# n64rgbv1.net
KiCad netlist of a schematic drawn in EAGLE
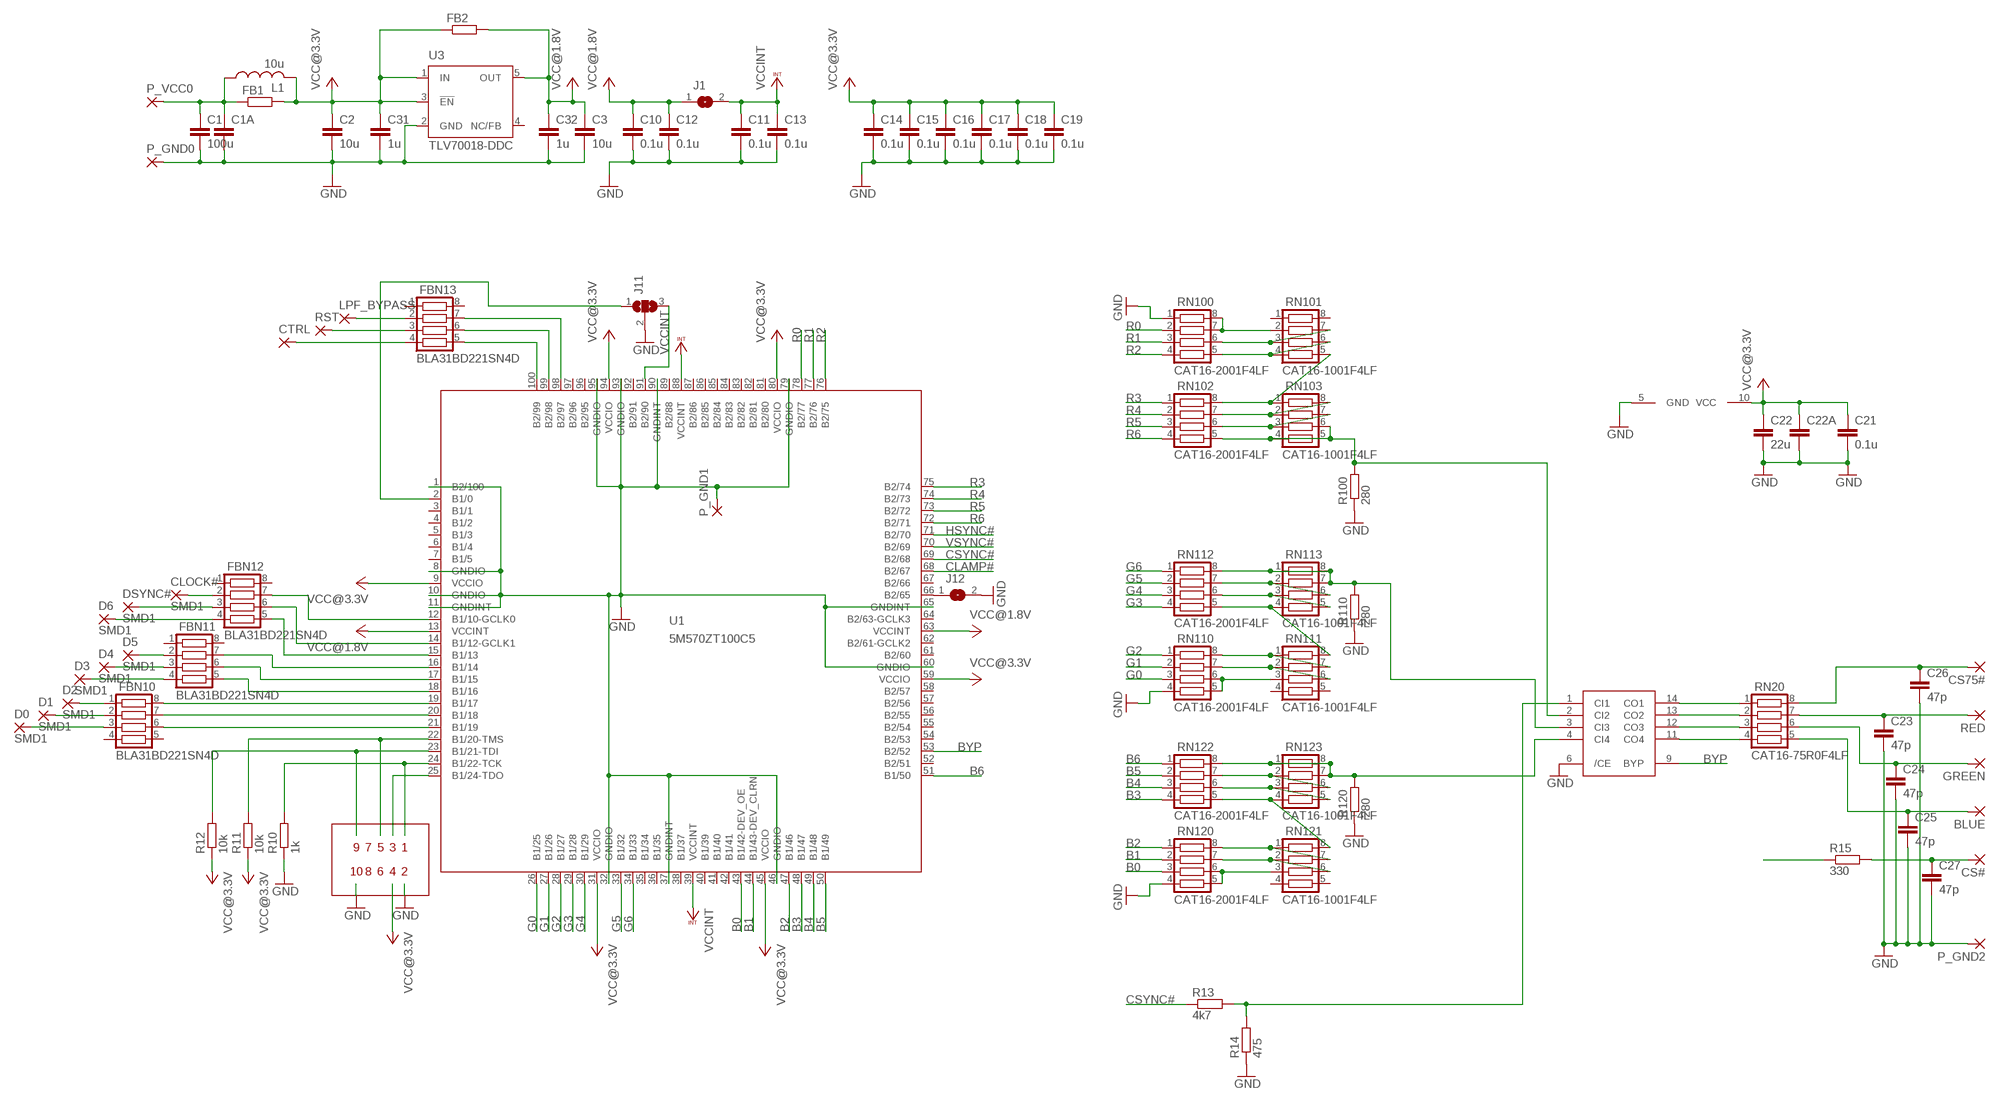
[diagram p0: schematic, sheet 1]

(export (version "E")
  (design (tool "Eeschema 10.0.6"))
  (components
    (comp (ref "BLUE")
      (value "SMD2")
      (footprint "eagle-import:SMD1,27-2,54")
      (libsource (lib "eagle-import") (part "SMD2"))
    )
    (comp (ref "C1")
      (value "100u")
      (footprint "eagle-import:C1206K")
      (libsource (lib "eagle-import") (part "C-EUC1206K"))
    )
    (comp (ref "C1A")
      (value "C-EUC0805")
      (footprint "eagle-import:C0805")
      (libsource (lib "eagle-import") (part "C-EUC0805"))
    )
    (comp (ref "C2")
      (value "10u")
      (footprint "eagle-import:C0805")
      (libsource (lib "eagle-import") (part "C-EUC0805"))
    )
    (comp (ref "C3")
      (value "10u")
      (footprint "eagle-import:C0805")
      (libsource (lib "eagle-import") (part "C-EUC0805"))
    )
    (comp (ref "C10")
      (value "0.1u")
      (footprint "eagle-import:C0603")
      (libsource (lib "eagle-import") (part "C-EUC0603"))
    )
    (comp (ref "C11")
      (value "0.1u")
      (footprint "eagle-import:C0603")
      (libsource (lib "eagle-import") (part "C-EUC0603"))
    )
    (comp (ref "C12")
      (value "0.1u")
      (footprint "eagle-import:C0603")
      (libsource (lib "eagle-import") (part "C-EUC0603"))
    )
    (comp (ref "C13")
      (value "0.1u")
      (footprint "eagle-import:C0603")
      (libsource (lib "eagle-import") (part "C-EUC0603"))
    )
    (comp (ref "C14")
      (value "0.1u")
      (footprint "eagle-import:C0603")
      (libsource (lib "eagle-import") (part "C-EUC0603"))
    )
    (comp (ref "C15")
      (value "0.1u")
      (footprint "eagle-import:C0603")
      (libsource (lib "eagle-import") (part "C-EUC0603"))
    )
    (comp (ref "C16")
      (value "0.1u")
      (footprint "eagle-import:C0603")
      (libsource (lib "eagle-import") (part "C-EUC0603"))
    )
    (comp (ref "C17")
      (value "0.1u")
      (footprint "eagle-import:C0603")
      (libsource (lib "eagle-import") (part "C-EUC0603"))
    )
    (comp (ref "C18")
      (value "0.1u")
      (footprint "eagle-import:C0603")
      (libsource (lib "eagle-import") (part "C-EUC0603"))
    )
    (comp (ref "C19")
      (value "0.1u")
      (footprint "eagle-import:C0603")
      (libsource (lib "eagle-import") (part "C-EUC0603"))
    )
    (comp (ref "C21")
      (value "0.1u")
      (footprint "eagle-import:C0603")
      (libsource (lib "eagle-import") (part "C-EUC0603"))
    )
    (comp (ref "C22")
      (value "22u")
      (footprint "eagle-import:C1206K")
      (libsource (lib "eagle-import") (part "C-EUC1206K"))
    )
    (comp (ref "C22A")
      (value "C-EUC0805")
      (footprint "eagle-import:C0805")
      (libsource (lib "eagle-import") (part "C-EUC0805"))
    )
    (comp (ref "C23")
      (value "47p")
      (footprint "eagle-import:C0603")
      (libsource (lib "eagle-import") (part "C-EUC0603"))
    )
    (comp (ref "C24")
      (value "47p")
      (footprint "eagle-import:C0603")
      (libsource (lib "eagle-import") (part "C-EUC0603"))
    )
    (comp (ref "C25")
      (value "47p")
      (footprint "eagle-import:C0603")
      (libsource (lib "eagle-import") (part "C-EUC0603"))
    )
    (comp (ref "C26")
      (value "47p")
      (footprint "eagle-import:C0603")
      (libsource (lib "eagle-import") (part "C-EUC0603"))
    )
    (comp (ref "C27")
      (value "47p")
      (footprint "eagle-import:C0603")
      (libsource (lib "eagle-import") (part "C-EUC0603"))
    )
    (comp (ref "C31")
      (value "1u")
      (footprint "eagle-import:C0603")
      (libsource (lib "eagle-import") (part "C-EUC0603"))
    )
    (comp (ref "C32")
      (value "1u")
      (footprint "eagle-import:C0603")
      (libsource (lib "eagle-import") (part "C-EUC0603"))
    )
    (comp (ref "CLOCK#")
      (value "SMD1")
      (footprint "eagle-import:SMD0,8-1,6")
      (libsource (lib "eagle-import") (part "SMD1"))
    )
    (comp (ref "CS#")
      (value "SMD2")
      (footprint "eagle-import:SMD1,27-2,54")
      (libsource (lib "eagle-import") (part "SMD2"))
    )
    (comp (ref "CS75#")
      (value "SMD2")
      (footprint "eagle-import:SMD1,27-2,54")
      (libsource (lib "eagle-import") (part "SMD2"))
    )
    (comp (ref "CTRL")
      (value "SMD2")
      (footprint "eagle-import:SMD1,27-2,54")
      (libsource (lib "eagle-import") (part "SMD2"))
    )
    (comp (ref "D0")
      (value "SMD1")
      (footprint "eagle-import:SMD0,8-1,6")
      (libsource (lib "eagle-import") (part "SMD1"))
    )
    (comp (ref "D1")
      (value "SMD1")
      (footprint "eagle-import:SMD0,8-1,6")
      (libsource (lib "eagle-import") (part "SMD1"))
    )
    (comp (ref "D2")
      (value "SMD1")
      (footprint "eagle-import:SMD0,8-1,6")
      (libsource (lib "eagle-import") (part "SMD1"))
    )
    (comp (ref "D3")
      (value "SMD1")
      (footprint "eagle-import:SMD0,8-1,6")
      (libsource (lib "eagle-import") (part "SMD1"))
    )
    (comp (ref "D4")
      (value "SMD1")
      (footprint "eagle-import:SMD0,8-1,6")
      (libsource (lib "eagle-import") (part "SMD1"))
    )
    (comp (ref "D5")
      (value "SMD1")
      (footprint "eagle-import:SMD0,8-1,6")
      (libsource (lib "eagle-import") (part "SMD1"))
    )
    (comp (ref "D6")
      (value "SMD1")
      (footprint "eagle-import:SMD0,8-1,6")
      (libsource (lib "eagle-import") (part "SMD1"))
    )
    (comp (ref "DSYNC#")
      (value "SMD1")
      (footprint "eagle-import:SMD0,8-1,6")
      (libsource (lib "eagle-import") (part "SMD1"))
    )
    (comp (ref "FB1")
      (value "R-EU_R0603")
      (footprint "eagle-import:R0603")
      (libsource (lib "eagle-import") (part "R-EU_R0603"))
    )
    (comp (ref "FB2")
      (value "R-EU_R0603")
      (footprint "eagle-import:R0603")
      (libsource (lib "eagle-import") (part "R-EU_R0603"))
    )
    (comp (ref "FBN10")
      (value "BLA31BD221SN4D")
      (footprint "eagle-import:CTS742C083")
      (libsource (lib "eagle-import") (part "CTS742C083"))
    )
    (comp (ref "FBN11")
      (value "BLA31BD221SN4D")
      (footprint "eagle-import:CTS742C083")
      (libsource (lib "eagle-import") (part "CTS742C083"))
    )
    (comp (ref "FBN12")
      (value "BLA31BD221SN4D")
      (footprint "eagle-import:CTS742C083")
      (libsource (lib "eagle-import") (part "CTS742C083"))
    )
    (comp (ref "FBN13")
      (value "BLA31BD221SN4D")
      (footprint "eagle-import:CTS742C083")
      (libsource (lib "eagle-import") (part "CTS742C083"))
    )
    (comp (ref "GREEN")
      (value "SMD2")
      (footprint "eagle-import:SMD1,27-2,54")
      (libsource (lib "eagle-import") (part "SMD2"))
    )
    (comp (ref "J1") (value "SJ") (footprint "eagle-import:SJ") (libsource (lib "eagle-import") (part "SJ")))
    (comp (ref "J11")
      (value "SJ2W")
      (footprint "eagle-import:SJ_2")
      (libsource (lib "eagle-import") (part "SJ2W"))
    )
    (comp (ref "J12") (value "SJ") (footprint "eagle-import:SJ") (libsource (lib "eagle-import") (part "SJ")))
    (comp (ref "L1")
      (value "10u")
      (footprint "eagle-import:L3230M")
      (libsource (lib "eagle-import") (part "L-USL3230M"))
    )
    (comp (ref "LPF_BYPASS")
      (value "SMD2")
      (footprint "eagle-import:SMD1,27-2,54")
      (libsource (lib "eagle-import") (part "SMD2"))
    )
    (comp (ref "P_GND0")
      (value "SMD2")
      (footprint "eagle-import:SMD1,27-2,54")
      (libsource (lib "eagle-import") (part "SMD2"))
    )
    (comp (ref "P_GND1")
      (value "SMD2")
      (footprint "eagle-import:SMD1,27-2,54")
      (libsource (lib "eagle-import") (part "SMD2"))
    )
    (comp (ref "P_GND2")
      (value "SMD2")
      (footprint "eagle-import:SMD1,27-2,54")
      (libsource (lib "eagle-import") (part "SMD2"))
    )
    (comp (ref "P_VCC0")
      (value "SMD2")
      (footprint "eagle-import:SMD1,27-2,54")
      (libsource (lib "eagle-import") (part "SMD2"))
    )
    (comp (ref "R10")
      (value "1k")
      (footprint "eagle-import:R0603")
      (libsource (lib "eagle-import") (part "R-EU_R0603"))
    )
    (comp (ref "R11")
      (value "10k")
      (footprint "eagle-import:R0603")
      (libsource (lib "eagle-import") (part "R-EU_R0603"))
    )
    (comp (ref "R12")
      (value "10k")
      (footprint "eagle-import:R0603")
      (libsource (lib "eagle-import") (part "R-EU_R0603"))
    )
    (comp (ref "R13")
      (value "4k7")
      (footprint "eagle-import:R0603")
      (libsource (lib "eagle-import") (part "R-EU_R0603"))
    )
    (comp (ref "R14")
      (value "475")
      (footprint "eagle-import:R0603")
      (libsource (lib "eagle-import") (part "R-EU_R0603"))
    )
    (comp (ref "R15")
      (value "330")
      (footprint "eagle-import:R0603")
      (libsource (lib "eagle-import") (part "R-EU_R0603"))
    )
    (comp (ref "R100")
      (value "280")
      (footprint "eagle-import:R0603")
      (libsource (lib "eagle-import") (part "R-EU_R0603"))
    )
    (comp (ref "R110")
      (value "280")
      (footprint "eagle-import:R0603")
      (libsource (lib "eagle-import") (part "R-EU_R0603"))
    )
    (comp (ref "R120")
      (value "280")
      (footprint "eagle-import:R0603")
      (libsource (lib "eagle-import") (part "R-EU_R0603"))
    )
    (comp (ref "RED")
      (value "SMD2")
      (footprint "eagle-import:SMD1,27-2,54")
      (libsource (lib "eagle-import") (part "SMD2"))
    )
    (comp (ref "RN20")
      (value "CAT16-75R0F4LF")
      (footprint "eagle-import:CTS742C083")
      (libsource (lib "eagle-import") (part "CTS742C083"))
    )
    (comp (ref "RN100")
      (value "CAT16-2001F4LF")
      (footprint "eagle-import:CTS742C083")
      (libsource (lib "eagle-import") (part "CTS742C083"))
    )
    (comp (ref "RN101")
      (value "CAT16-1001F4LF")
      (footprint "eagle-import:CTS742C083")
      (libsource (lib "eagle-import") (part "CTS742C083"))
    )
    (comp (ref "RN102")
      (value "CAT16-2001F4LF")
      (footprint "eagle-import:CTS742C083")
      (libsource (lib "eagle-import") (part "CTS742C083"))
    )
    (comp (ref "RN103")
      (value "CAT16-1001F4LF")
      (footprint "eagle-import:CTS742C083")
      (libsource (lib "eagle-import") (part "CTS742C083"))
    )
    (comp (ref "RN110")
      (value "CAT16-2001F4LF")
      (footprint "eagle-import:CTS742C083")
      (libsource (lib "eagle-import") (part "CTS742C083"))
    )
    (comp (ref "RN111")
      (value "CAT16-1001F4LF")
      (footprint "eagle-import:CTS742C083")
      (libsource (lib "eagle-import") (part "CTS742C083"))
    )
    (comp (ref "RN112")
      (value "CAT16-2001F4LF")
      (footprint "eagle-import:CTS742C083")
      (libsource (lib "eagle-import") (part "CTS742C083"))
    )
    (comp (ref "RN113")
      (value "CAT16-1001F4LF")
      (footprint "eagle-import:CTS742C083")
      (libsource (lib "eagle-import") (part "CTS742C083"))
    )
    (comp (ref "RN120")
      (value "CAT16-2001F4LF")
      (footprint "eagle-import:CTS742C083")
      (libsource (lib "eagle-import") (part "CTS742C083"))
    )
    (comp (ref "RN121")
      (value "CAT16-1001F4LF")
      (footprint "eagle-import:CTS742C083")
      (libsource (lib "eagle-import") (part "CTS742C083"))
    )
    (comp (ref "RN122")
      (value "CAT16-2001F4LF")
      (footprint "eagle-import:CTS742C083")
      (libsource (lib "eagle-import") (part "CTS742C083"))
    )
    (comp (ref "RN123")
      (value "CAT16-1001F4LF")
      (footprint "eagle-import:CTS742C083")
      (libsource (lib "eagle-import") (part "CTS742C083"))
    )
    (comp (ref "RST")
      (value "SMD2")
      (footprint "eagle-import:SMD1,27-2,54")
      (libsource (lib "eagle-import") (part "SMD2"))
    )
    (comp (ref "U1")
      (value "5M570ZT100C5")
      (footprint "eagle-import:TQFP100")
      (libsource (lib "eagle-import") (part "5M570ZT100C5"))
    )
    (comp (ref "U2")
      (value "THS7374")
      (footprint "eagle-import:THS7374")
      (libsource (lib "eagle-import") (part "THS7374"))
    )
    (comp (ref "U3")
      (value "TLV70018-DDC")
      (footprint "eagle-import:SOT23-DBV")
      (fields (field (name "MF") "TEXAS INSTRUMENT CONNECTORS") (field (name "MPN") "TPS77018DBVR"))
      (libsource (lib "eagle-import") (part "TPS77018"))
    )
  )
  (nets
    (net (code "1") (name "/B0") (class "Default")
      (node (ref "RN120") (pin "3") (pinfunction "3_3") (pintype "passive"))
      (node (ref "U1") (pin "43") (pinfunction "B1/42-DEV_OE_43") (pintype "bidirectional"))
    )
    (net (code "2") (name "/B1") (class "Default")
      (node (ref "RN120") (pin "2") (pinfunction "2_2") (pintype "passive"))
      (node (ref "U1") (pin "44") (pinfunction "B1/43-DEV_CLRN_44") (pintype "bidirectional"))
    )
    (net (code "3") (name "/B2") (class "Default")
      (node (ref "RN120") (pin "1") (pinfunction "1_1") (pintype "passive"))
      (node (ref "U1") (pin "47") (pinfunction "B1/46_47") (pintype "bidirectional"))
    )
    (net (code "4") (name "/B3") (class "Default")
      (node (ref "RN122") (pin "4") (pinfunction "4_4") (pintype "passive"))
      (node (ref "U1") (pin "48") (pinfunction "B1/47_48") (pintype "bidirectional"))
    )
    (net (code "5") (name "/B4") (class "Default")
      (node (ref "RN122") (pin "3") (pinfunction "3_3") (pintype "passive"))
      (node (ref "U1") (pin "49") (pinfunction "B1/48_49") (pintype "bidirectional"))
    )
    (net (code "6") (name "/B5") (class "Default")
      (node (ref "RN122") (pin "2") (pinfunction "2_2") (pintype "passive"))
      (node (ref "U1") (pin "50") (pinfunction "B1/49_50") (pintype "bidirectional"))
    )
    (net (code "7") (name "/B6") (class "Default")
      (node (ref "RN122") (pin "1") (pinfunction "1_1") (pintype "passive"))
      (node (ref "U1") (pin "51") (pinfunction "B1/50_51") (pintype "bidirectional"))
    )
    (net (code "8") (name "/BYP") (class "Default")
      (node (ref "U1") (pin "53") (pinfunction "B2/52_53") (pintype "bidirectional"))
      (node (ref "U2") (pin "9") (pinfunction "BYP_9") (pintype "bidirectional"))
    )
    (net (code "9") (name "/CLAMP#") (class "Default")
      (node (ref "U1") (pin "68") (pinfunction "B2/67_68") (pintype "bidirectional"))
    )
    (net (code "10") (name "/CSYNC#") (class "Default")
      (node (ref "R13") (pin "1") (pinfunction "1_1") (pintype "passive"))
      (node (ref "R15") (pin "1") (pinfunction "1_1") (pintype "passive"))
      (node (ref "U1") (pin "69") (pinfunction "B2/68_69") (pintype "bidirectional"))
    )
    (net (code "11") (name "/G0") (class "Default")
      (node (ref "RN110") (pin "3") (pinfunction "3_3") (pintype "passive"))
      (node (ref "U1") (pin "26") (pinfunction "B1/25_26") (pintype "bidirectional"))
    )
    (net (code "12") (name "/G1") (class "Default")
      (node (ref "RN110") (pin "2") (pinfunction "2_2") (pintype "passive"))
      (node (ref "U1") (pin "27") (pinfunction "B1/26_27") (pintype "bidirectional"))
    )
    (net (code "13") (name "/G2") (class "Default")
      (node (ref "RN110") (pin "1") (pinfunction "1_1") (pintype "passive"))
      (node (ref "U1") (pin "28") (pinfunction "B1/27_28") (pintype "bidirectional"))
    )
    (net (code "14") (name "/G3") (class "Default")
      (node (ref "RN112") (pin "4") (pinfunction "4_4") (pintype "passive"))
      (node (ref "U1") (pin "29") (pinfunction "B1/28_29") (pintype "bidirectional"))
    )
    (net (code "15") (name "/G4") (class "Default")
      (node (ref "RN112") (pin "3") (pinfunction "3_3") (pintype "passive"))
      (node (ref "U1") (pin "30") (pinfunction "B1/29_30") (pintype "bidirectional"))
    )
    (net (code "16") (name "/G5") (class "Default")
      (node (ref "RN112") (pin "2") (pinfunction "2_2") (pintype "passive"))
      (node (ref "U1") (pin "33") (pinfunction "B1/32_33") (pintype "bidirectional"))
    )
    (net (code "17") (name "/G6") (class "Default")
      (node (ref "RN112") (pin "1") (pinfunction "1_1") (pintype "passive"))
      (node (ref "U1") (pin "34") (pinfunction "B1/33_34") (pintype "bidirectional"))
    )
    (net (code "18") (name "/HSYNC#") (class "Default")
      (node (ref "U1") (pin "71") (pinfunction "B2/70_71") (pintype "bidirectional"))
    )
    (net (code "19") (name "/R0") (class "Default")
      (node (ref "RN100") (pin "2") (pinfunction "2_2") (pintype "passive"))
      (node (ref "U1") (pin "78") (pinfunction "B2/77_78") (pintype "bidirectional"))
    )
    (net (code "20") (name "/R1") (class "Default")
      (node (ref "RN100") (pin "3") (pinfunction "3_3") (pintype "passive"))
      (node (ref "U1") (pin "77") (pinfunction "B2/76_77") (pintype "bidirectional"))
    )
    (net (code "21") (name "/R2") (class "Default")
      (node (ref "RN100") (pin "4") (pinfunction "4_4") (pintype "passive"))
      (node (ref "U1") (pin "76") (pinfunction "B2/75_76") (pintype "bidirectional"))
    )
    (net (code "22") (name "/R3") (class "Default")
      (node (ref "RN102") (pin "1") (pinfunction "1_1") (pintype "passive"))
      (node (ref "U1") (pin "75") (pinfunction "B2/74_75") (pintype "bidirectional"))
    )
    (net (code "23") (name "/R4") (class "Default")
      (node (ref "RN102") (pin "2") (pinfunction "2_2") (pintype "passive"))
      (node (ref "U1") (pin "74") (pinfunction "B2/73_74") (pintype "bidirectional"))
    )
    (net (code "24") (name "/R5") (class "Default")
      (node (ref "RN102") (pin "3") (pinfunction "3_3") (pintype "passive"))
      (node (ref "U1") (pin "73") (pinfunction "B2/72_73") (pintype "bidirectional"))
    )
    (net (code "25") (name "/R6") (class "Default")
      (node (ref "RN102") (pin "4") (pinfunction "4_4") (pintype "passive"))
      (node (ref "U1") (pin "72") (pinfunction "B2/71_72") (pintype "bidirectional"))
    )
    (net (code "26") (name "/VSYNC#") (class "Default")
      (node (ref "U1") (pin "70") (pinfunction "B2/69_70") (pintype "bidirectional"))
    )
    (net (code "27") (name "GND") (class "Default")
      (node (ref "C1") (pin "2") (pinfunction "2_2") (pintype "passive"))
      (node (ref "C10") (pin "2") (pinfunction "2_2") (pintype "passive"))
      (node (ref "C11") (pin "2") (pinfunction "2_2") (pintype "passive"))
      (node (ref "C12") (pin "2") (pinfunction "2_2") (pintype "passive"))
      (node (ref "C13") (pin "2") (pinfunction "2_2") (pintype "passive"))
      (node (ref "C14") (pin "2") (pinfunction "2_2") (pintype "passive"))
      (node (ref "C15") (pin "2") (pinfunction "2_2") (pintype "passive"))
      (node (ref "C16") (pin "2") (pinfunction "2_2") (pintype "passive"))
      (node (ref "C17") (pin "2") (pinfunction "2_2") (pintype "passive"))
      (node (ref "C18") (pin "2") (pinfunction "2_2") (pintype "passive"))
      (node (ref "C19") (pin "2") (pinfunction "2_2") (pintype "passive"))
      (node (ref "C1A") (pin "2") (pinfunction "2_2") (pintype "passive"))
      (node (ref "C2") (pin "2") (pinfunction "2_2") (pintype "passive"))
      (node (ref "C21") (pin "2") (pinfunction "2_2") (pintype "passive"))
      (node (ref "C22") (pin "2") (pinfunction "2_2") (pintype "passive"))
      (node (ref "C22A") (pin "2") (pinfunction "2_2") (pintype "passive"))
      (node (ref "C23") (pin "2") (pinfunction "2_2") (pintype "passive"))
      (node (ref "C24") (pin "2") (pinfunction "2_2") (pintype "passive"))
      (node (ref "C25") (pin "2") (pinfunction "2_2") (pintype "passive"))
      (node (ref "C26") (pin "2") (pinfunction "2_2") (pintype "passive"))
      (node (ref "C27") (pin "2") (pinfunction "2_2") (pintype "passive"))
      (node (ref "C3") (pin "2") (pinfunction "2_2") (pintype "passive"))
      (node (ref "C31") (pin "2") (pinfunction "2_2") (pintype "passive"))
      (node (ref "C32") (pin "2") (pinfunction "2_2") (pintype "passive"))
      (node (ref "J11") (pin "2") (pinfunction "2_2") (pintype "passive"))
      (node (ref "J12") (pin "2") (pinfunction "2_2") (pintype "passive"))
      (node (ref "P_GND0") (pin "1") (pinfunction "P_1") (pintype "passive"))
      (node (ref "P_GND1") (pin "1") (pinfunction "P_1") (pintype "passive"))
      (node (ref "P_GND2") (pin "1") (pinfunction "P_1") (pintype "passive"))
      (node (ref "R10") (pin "1") (pinfunction "1_1") (pintype "passive"))
      (node (ref "R100") (pin "1") (pinfunction "1_1") (pintype "passive"))
      (node (ref "R110") (pin "1") (pinfunction "1_1") (pintype "passive"))
      (node (ref "R120") (pin "1") (pinfunction "1_1") (pintype "passive"))
      (node (ref "R14") (pin "1") (pinfunction "1_1") (pintype "passive"))
      (node (ref "RN100") (pin "1") (pinfunction "1_1") (pintype "passive"))
      (node (ref "RN110") (pin "4") (pinfunction "4_4") (pintype "passive"))
      (node (ref "RN120") (pin "4") (pinfunction "4_4") (pintype "passive"))
      (node (ref "U1") (pin "1") (pinfunction "B2/100_1") (pintype "bidirectional"))
      (node (ref "U1") (pin "10") (pinfunction "GNDIO_10") (pintype "power_in"))
      (node (ref "U1") (pin "11") (pinfunction "GNDINT_11") (pintype "power_in"))
      (node (ref "U1") (pin "32") (pinfunction "GNDIO_32") (pintype "power_in"))
      (node (ref "U1") (pin "37") (pinfunction "GNDINT_37") (pintype "power_in"))
      (node (ref "U1") (pin "46") (pinfunction "GNDIO_46") (pintype "power_in"))
      (node (ref "U1") (pin "60") (pinfunction "GNDIO_60") (pintype "power_in"))
      (node (ref "U1") (pin "65") (pinfunction "GNDINT_65") (pintype "power_in"))
      (node (ref "U1") (pin "79") (pinfunction "GNDIO_79") (pintype "power_in"))
      (node (ref "U1") (pin "8") (pinfunction "GNDIO_8") (pintype "power_in"))
      (node (ref "U1") (pin "90") (pinfunction "GNDINT_90") (pintype "power_in"))
      (node (ref "U1") (pin "93") (pinfunction "GNDIO_93") (pintype "power_in"))
      (node (ref "U1") (pin "95") (pinfunction "GNDIO_95") (pintype "power_in"))
      (node (ref "U2") (pin "5") (pinfunction "GND_5") (pintype "bidirectional"))
      (node (ref "U2") (pin "6") (pinfunction "/CE_6") (pintype "bidirectional"))
      (node (ref "U3") (pin "2") (pinfunction "GND_2") (pintype "power_in"))
    )
    (net (code "28") (name "Net-(BLUE-P)") (class "Default")
      (node (ref "BLUE") (pin "1") (pinfunction "P_1") (pintype "passive"))
      (node (ref "C25") (pin "1") (pinfunction "1_1") (pintype "passive"))
      (node (ref "RN20") (pin "5") (pinfunction "5_5") (pintype "passive"))
    )
    (net (code "29") (name "Net-(CLOCK#-P)") (class "Default")
      (node (ref "CLOCK#") (pin "P$1") (pinfunction "P_P$1") (pintype "passive"))
      (node (ref "FBN12") (pin "2") (pinfunction "2_2") (pintype "passive"))
    )
    (net (code "30") (name "Net-(CS#-P)") (class "Default")
      (node (ref "C27") (pin "1") (pinfunction "1_1") (pintype "passive"))
      (node (ref "CS#") (pin "1") (pinfunction "P_1") (pintype "passive"))
      (node (ref "R15") (pin "2") (pinfunction "2_2") (pintype "passive"))
    )
    (net (code "31") (name "Net-(CS75#-P)") (class "Default")
      (node (ref "C26") (pin "1") (pinfunction "1_1") (pintype "passive"))
      (node (ref "CS75#") (pin "1") (pinfunction "P_1") (pintype "passive"))
      (node (ref "RN20") (pin "8") (pinfunction "8_8") (pintype "passive"))
    )
    (net (code "32") (name "Net-(CTRL-P)") (class "Default")
      (node (ref "CTRL") (pin "1") (pinfunction "P_1") (pintype "passive"))
      (node (ref "FBN13") (pin "4") (pinfunction "4_4") (pintype "passive"))
    )
    (net (code "33") (name "Net-(D0-P)") (class "Default")
      (node (ref "D0") (pin "P$1") (pinfunction "P_P$1") (pintype "passive"))
      (node (ref "FBN10") (pin "3") (pinfunction "3_3") (pintype "passive"))
    )
    (net (code "34") (name "Net-(D1-P)") (class "Default")
      (node (ref "D1") (pin "P$1") (pinfunction "P_P$1") (pintype "passive"))
      (node (ref "FBN10") (pin "2") (pinfunction "2_2") (pintype "passive"))
    )
    (net (code "35") (name "Net-(D2-P)") (class "Default")
      (node (ref "D2") (pin "P$1") (pinfunction "P_P$1") (pintype "passive"))
      (node (ref "FBN10") (pin "1") (pinfunction "1_1") (pintype "passive"))
    )
    (net (code "36") (name "Net-(D3-P)") (class "Default")
      (node (ref "D3") (pin "P$1") (pinfunction "P_P$1") (pintype "passive"))
      (node (ref "FBN11") (pin "4") (pinfunction "4_4") (pintype "passive"))
    )
    (net (code "37") (name "Net-(D4-P)") (class "Default")
      (node (ref "D4") (pin "P$1") (pinfunction "P_P$1") (pintype "passive"))
      (node (ref "FBN11") (pin "3") (pinfunction "3_3") (pintype "passive"))
    )
    (net (code "38") (name "Net-(D5-P)") (class "Default")
      (node (ref "D5") (pin "P$1") (pinfunction "P_P$1") (pintype "passive"))
      (node (ref "FBN11") (pin "2") (pinfunction "2_2") (pintype "passive"))
    )
    (net (code "39") (name "Net-(D6-P)") (class "Default")
      (node (ref "D6") (pin "P$1") (pinfunction "P_P$1") (pintype "passive"))
      (node (ref "FBN12") (pin "4") (pinfunction "4_4") (pintype "passive"))
    )
    (net (code "40") (name "Net-(DSYNC#-P)") (class "Default")
      (node (ref "DSYNC#") (pin "P$1") (pinfunction "P_P$1") (pintype "passive"))
      (node (ref "FBN12") (pin "3") (pinfunction "3_3") (pintype "passive"))
    )
    (net (code "41") (name "Net-(GREEN-P)") (class "Default")
      (node (ref "C24") (pin "1") (pinfunction "1_1") (pintype "passive"))
      (node (ref "GREEN") (pin "1") (pinfunction "P_1") (pintype "passive"))
      (node (ref "RN20") (pin "6") (pinfunction "6_6") (pintype "passive"))
    )
    (net (code "42") (name "Net-(LPF_BYPASS-P)") (class "Default")
      (node (ref "FBN13") (pin "2") (pinfunction "2_2") (pintype "passive"))
      (node (ref "LPF_BYPASS") (pin "1") (pinfunction "P_1") (pintype "passive"))
    )
    (net (code "43") (name "Net-(P_VCC0-P)") (class "Default")
      (node (ref "C1") (pin "1") (pinfunction "1_1") (pintype "passive"))
      (node (ref "C1A") (pin "1") (pinfunction "1_1") (pintype "passive"))
      (node (ref "FB1") (pin "1") (pinfunction "1_1") (pintype "passive"))
      (node (ref "L1") (pin "1") (pinfunction "1_1") (pintype "passive"))
      (node (ref "P_VCC0") (pin "1") (pinfunction "P_1") (pintype "passive"))
    )
    (net (code "44") (name "Net-(RED-P)") (class "Default")
      (node (ref "C23") (pin "1") (pinfunction "1_1") (pintype "passive"))
      (node (ref "RED") (pin "1") (pinfunction "P_1") (pintype "passive"))
      (node (ref "RN20") (pin "7") (pinfunction "7_7") (pintype "passive"))
    )
    (net (code "45") (name "Net-(RN100-Pad5)") (class "Default")
      (node (ref "RN100") (pin "5") (pinfunction "5_5") (pintype "passive"))
      (node (ref "RN101") (pin "4") (pinfunction "4_4") (pintype "passive"))
      (node (ref "RN101") (pin "6") (pinfunction "6_6") (pintype "passive"))
    )
    (net (code "46") (name "Net-(RN100-Pad6)") (class "Default")
      (node (ref "RN100") (pin "6") (pinfunction "6_6") (pintype "passive"))
      (node (ref "RN101") (pin "3") (pinfunction "3_3") (pintype "passive"))
      (node (ref "RN101") (pin "7") (pinfunction "7_7") (pintype "passive"))
    )
    (net (code "47") (name "Net-(RN100-Pad7)") (class "Default")
      (node (ref "RN100") (pin "7") (pinfunction "7_7") (pintype "passive"))
      (node (ref "RN100") (pin "8") (pinfunction "8_8") (pintype "passive"))
      (node (ref "RN101") (pin "2") (pinfunction "2_2") (pintype "passive"))
    )
    (net (code "48") (name "Net-(RN101-Pad5)") (class "Default")
      (node (ref "RN101") (pin "5") (pinfunction "5_5") (pintype "passive"))
      (node (ref "RN102") (pin "8") (pinfunction "8_8") (pintype "passive"))
      (node (ref "RN103") (pin "1") (pinfunction "1_1") (pintype "passive"))
    )
    (net (code "49") (name "Net-(RN102-Pad6)") (class "Default")
      (node (ref "RN102") (pin "6") (pinfunction "6_6") (pintype "passive"))
      (node (ref "RN103") (pin "3") (pinfunction "3_3") (pintype "passive"))
      (node (ref "RN103") (pin "7") (pinfunction "7_7") (pintype "passive"))
    )
    (net (code "50") (name "Net-(RN102-Pad7)") (class "Default")
      (node (ref "RN102") (pin "7") (pinfunction "7_7") (pintype "passive"))
      (node (ref "RN103") (pin "2") (pinfunction "2_2") (pintype "passive"))
      (node (ref "RN103") (pin "8") (pinfunction "8_8") (pintype "passive"))
    )
    (net (code "51") (name "Net-(RN110-Pad5)") (class "Default")
      (node (ref "RN110") (pin "5") (pinfunction "5_5") (pintype "passive"))
      (node (ref "RN110") (pin "6") (pinfunction "6_6") (pintype "passive"))
      (node (ref "RN111") (pin "3") (pinfunction "3_3") (pintype "passive"))
    )
    (net (code "52") (name "Net-(RN110-Pad7)") (class "Default")
      (node (ref "RN110") (pin "7") (pinfunction "7_7") (pintype "passive"))
      (node (ref "RN111") (pin "2") (pinfunction "2_2") (pintype "passive"))
      (node (ref "RN111") (pin "6") (pinfunction "6_6") (pintype "passive"))
    )
    (net (code "53") (name "Net-(RN110-Pad8)") (class "Default")
      (node (ref "RN110") (pin "8") (pinfunction "8_8") (pintype "passive"))
      (node (ref "RN111") (pin "1") (pinfunction "1_1") (pintype "passive"))
      (node (ref "RN111") (pin "7") (pinfunction "7_7") (pintype "passive"))
    )
    (net (code "54") (name "Net-(RN111-Pad8)") (class "Default")
      (node (ref "RN111") (pin "8") (pinfunction "8_8") (pintype "passive"))
      (node (ref "RN112") (pin "5") (pinfunction "5_5") (pintype "passive"))
      (node (ref "RN113") (pin "4") (pinfunction "4_4") (pintype "passive"))
    )
    (net (code "55") (name "Net-(RN112-Pad6)") (class "Default")
      (node (ref "RN112") (pin "6") (pinfunction "6_6") (pintype "passive"))
      (node (ref "RN113") (pin "3") (pinfunction "3_3") (pintype "passive"))
      (node (ref "RN113") (pin "5") (pinfunction "5_5") (pintype "passive"))
    )
    (net (code "56") (name "Net-(RN112-Pad7)") (class "Default")
      (node (ref "RN112") (pin "7") (pinfunction "7_7") (pintype "passive"))
      (node (ref "RN113") (pin "2") (pinfunction "2_2") (pintype "passive"))
      (node (ref "RN113") (pin "6") (pinfunction "6_6") (pintype "passive"))
    )
    (net (code "57") (name "Net-(RN120-Pad5)") (class "Default")
      (node (ref "RN120") (pin "5") (pinfunction "5_5") (pintype "passive"))
      (node (ref "RN120") (pin "6") (pinfunction "6_6") (pintype "passive"))
      (node (ref "RN121") (pin "3") (pinfunction "3_3") (pintype "passive"))
    )
    (net (code "58") (name "Net-(RN120-Pad7)") (class "Default")
      (node (ref "RN120") (pin "7") (pinfunction "7_7") (pintype "passive"))
      (node (ref "RN121") (pin "2") (pinfunction "2_2") (pintype "passive"))
      (node (ref "RN121") (pin "6") (pinfunction "6_6") (pintype "passive"))
    )
    (net (code "59") (name "Net-(RN120-Pad8)") (class "Default")
      (node (ref "RN120") (pin "8") (pinfunction "8_8") (pintype "passive"))
      (node (ref "RN121") (pin "1") (pinfunction "1_1") (pintype "passive"))
      (node (ref "RN121") (pin "7") (pinfunction "7_7") (pintype "passive"))
    )
    (net (code "60") (name "Net-(RN121-Pad8)") (class "Default")
      (node (ref "RN121") (pin "8") (pinfunction "8_8") (pintype "passive"))
      (node (ref "RN122") (pin "5") (pinfunction "5_5") (pintype "passive"))
      (node (ref "RN123") (pin "4") (pinfunction "4_4") (pintype "passive"))
    )
    (net (code "61") (name "Net-(RN122-Pad6)") (class "Default")
      (node (ref "RN122") (pin "6") (pinfunction "6_6") (pintype "passive"))
      (node (ref "RN123") (pin "3") (pinfunction "3_3") (pintype "passive"))
      (node (ref "RN123") (pin "5") (pinfunction "5_5") (pintype "passive"))
    )
    (net (code "62") (name "Net-(RN122-Pad7)") (class "Default")
      (node (ref "RN122") (pin "7") (pinfunction "7_7") (pintype "passive"))
      (node (ref "RN123") (pin "2") (pinfunction "2_2") (pintype "passive"))
      (node (ref "RN123") (pin "6") (pinfunction "6_6") (pintype "passive"))
    )
    (net (code "63") (name "Net-(RST-P)") (class "Default")
      (node (ref "FBN13") (pin "3") (pinfunction "3_3") (pintype "passive"))
      (node (ref "RST") (pin "1") (pinfunction "P_1") (pintype "passive"))
    )
    (net (code "64") (name "Net-(U1-B1{slash}0)") (class "Default")
      (node (ref "J11") (pin "1") (pinfunction "1_1") (pintype "passive"))
      (node (ref "U1") (pin "2") (pinfunction "B1/0_2") (pintype "bidirectional"))
    )
    (net (code "65") (name "Net-(U1-B1{slash}10-GCLK0)") (class "Default")
      (node (ref "FBN12") (pin "7") (pinfunction "7_7") (pintype "passive"))
      (node (ref "U1") (pin "12") (pinfunction "B1/10-GCLK0_12") (pintype "bidirectional"))
    )
    (net (code "66") (name "Net-(U1-B1{slash}12-GCLK1)") (class "Default")
      (node (ref "FBN12") (pin "6") (pinfunction "6_6") (pintype "passive"))
      (node (ref "U1") (pin "14") (pinfunction "B1/12-GCLK1_14") (pintype "bidirectional"))
    )
    (net (code "67") (name "Net-(U1-B1{slash}13)") (class "Default")
      (node (ref "FBN12") (pin "5") (pinfunction "5_5") (pintype "passive"))
      (node (ref "U1") (pin "15") (pinfunction "B1/13_15") (pintype "bidirectional"))
    )
    (net (code "68") (name "Net-(U1-B1{slash}14)") (class "Default")
      (node (ref "FBN11") (pin "7") (pinfunction "7_7") (pintype "passive"))
      (node (ref "U1") (pin "16") (pinfunction "B1/14_16") (pintype "bidirectional"))
    )
    (net (code "69") (name "Net-(U1-B1{slash}15)") (class "Default")
      (node (ref "FBN11") (pin "6") (pinfunction "6_6") (pintype "passive"))
      (node (ref "U1") (pin "17") (pinfunction "B1/15_17") (pintype "bidirectional"))
    )
    (net (code "70") (name "Net-(U1-B1{slash}16)") (class "Default")
      (node (ref "FBN11") (pin "5") (pinfunction "5_5") (pintype "passive"))
      (node (ref "U1") (pin "18") (pinfunction "B1/16_18") (pintype "bidirectional"))
    )
    (net (code "71") (name "Net-(U1-B1{slash}17)") (class "Default")
      (node (ref "FBN10") (pin "8") (pinfunction "8_8") (pintype "passive"))
      (node (ref "U1") (pin "19") (pinfunction "B1/17_19") (pintype "bidirectional"))
    )
    (net (code "72") (name "Net-(U1-B1{slash}18)") (class "Default")
      (node (ref "FBN10") (pin "7") (pinfunction "7_7") (pintype "passive"))
      (node (ref "U1") (pin "20") (pinfunction "B1/18_20") (pintype "bidirectional"))
    )
    (net (code "73") (name "Net-(U1-B1{slash}19)") (class "Default")
      (node (ref "FBN10") (pin "6") (pinfunction "6_6") (pintype "passive"))
      (node (ref "U1") (pin "21") (pinfunction "B1/19_21") (pintype "bidirectional"))
    )
    (net (code "74") (name "Net-(U1-B1{slash}20-TMS)") (class "Default")
      (node (ref "R11") (pin "2") (pinfunction "2_2") (pintype "passive"))
      (node (ref "U1") (pin "22") (pinfunction "B1/20-TMS_22") (pintype "input"))
    )
    (net (code "75") (name "Net-(U1-B1{slash}21-TDI)") (class "Default")
      (node (ref "R12") (pin "2") (pinfunction "2_2") (pintype "passive"))
      (node (ref "U1") (pin "23") (pinfunction "B1/21-TDI_23") (pintype "input"))
    )
    (net (code "76") (name "Net-(U1-B1{slash}22-TCK)") (class "Default")
      (node (ref "R10") (pin "2") (pinfunction "2_2") (pintype "passive"))
      (node (ref "U1") (pin "24") (pinfunction "B1/22-TCK_24") (pintype "input"))
    )
    (net (code "77") (name "Net-(U1-B2{slash}65)") (class "Default")
      (node (ref "J12") (pin "1") (pinfunction "1_1") (pintype "passive"))
      (node (ref "U1") (pin "66") (pinfunction "B2/65_66") (pintype "bidirectional"))
    )
    (net (code "78") (name "Net-(U1-B2{slash}90)") (class "Default")
      (node (ref "J11") (pin "3") (pinfunction "3_3") (pintype "passive"))
      (node (ref "U1") (pin "91") (pinfunction "B2/90_91") (pintype "bidirectional"))
    )
    (net (code "79") (name "Net-(U1-B2{slash}97)") (class "Default")
      (node (ref "FBN13") (pin "7") (pinfunction "7_7") (pintype "passive"))
      (node (ref "U1") (pin "98") (pinfunction "B2/97_98") (pintype "bidirectional"))
    )
    (net (code "80") (name "Net-(U1-B2{slash}98)") (class "Default")
      (node (ref "FBN13") (pin "6") (pinfunction "6_6") (pintype "passive"))
      (node (ref "U1") (pin "99") (pinfunction "B2/98_99") (pintype "bidirectional"))
    )
    (net (code "81") (name "Net-(U1-B2{slash}99)") (class "Default")
      (node (ref "FBN13") (pin "5") (pinfunction "5_5") (pintype "passive"))
      (node (ref "U1") (pin "100") (pinfunction "B2/99_100") (pintype "bidirectional"))
    )
    (net (code "82") (name "Net-(U2A-CI1)") (class "Default")
      (node (ref "R13") (pin "2") (pinfunction "2_2") (pintype "passive"))
      (node (ref "R14") (pin "2") (pinfunction "2_2") (pintype "passive"))
      (node (ref "U2") (pin "1") (pinfunction "CI1_1") (pintype "bidirectional"))
    )
    (net (code "83") (name "Net-(U2A-CI2)") (class "Default")
      (node (ref "R100") (pin "2") (pinfunction "2_2") (pintype "passive"))
      (node (ref "RN102") (pin "5") (pinfunction "5_5") (pintype "passive"))
      (node (ref "RN103") (pin "4") (pinfunction "4_4") (pintype "passive"))
      (node (ref "RN103") (pin "5") (pinfunction "5_5") (pintype "passive"))
      (node (ref "RN103") (pin "6") (pinfunction "6_6") (pintype "passive"))
      (node (ref "U2") (pin "2") (pinfunction "CI2_2") (pintype "bidirectional"))
    )
    (net (code "84") (name "Net-(U2A-CI3)") (class "Default")
      (node (ref "R110") (pin "2") (pinfunction "2_2") (pintype "passive"))
      (node (ref "RN112") (pin "8") (pinfunction "8_8") (pintype "passive"))
      (node (ref "RN113") (pin "1") (pinfunction "1_1") (pintype "passive"))
      (node (ref "RN113") (pin "7") (pinfunction "7_7") (pintype "passive"))
      (node (ref "RN113") (pin "8") (pinfunction "8_8") (pintype "passive"))
      (node (ref "U2") (pin "3") (pinfunction "CI3_3") (pintype "bidirectional"))
    )
    (net (code "85") (name "Net-(U2A-CI4)") (class "Default")
      (node (ref "R120") (pin "2") (pinfunction "2_2") (pintype "passive"))
      (node (ref "RN122") (pin "8") (pinfunction "8_8") (pintype "passive"))
      (node (ref "RN123") (pin "1") (pinfunction "1_1") (pintype "passive"))
      (node (ref "RN123") (pin "7") (pinfunction "7_7") (pintype "passive"))
      (node (ref "RN123") (pin "8") (pinfunction "8_8") (pintype "passive"))
      (node (ref "U2") (pin "4") (pinfunction "CI4_4") (pintype "bidirectional"))
    )
    (net (code "86") (name "Net-(U2A-CO1)") (class "Default")
      (node (ref "RN20") (pin "1") (pinfunction "1_1") (pintype "passive"))
      (node (ref "U2") (pin "14") (pinfunction "CO1_14") (pintype "bidirectional"))
    )
    (net (code "87") (name "Net-(U2A-CO2)") (class "Default")
      (node (ref "RN20") (pin "2") (pinfunction "2_2") (pintype "passive"))
      (node (ref "U2") (pin "13") (pinfunction "CO2_13") (pintype "bidirectional"))
    )
    (net (code "88") (name "Net-(U2A-CO3)") (class "Default")
      (node (ref "RN20") (pin "3") (pinfunction "3_3") (pintype "passive"))
      (node (ref "U2") (pin "12") (pinfunction "CO3_12") (pintype "bidirectional"))
    )
    (net (code "89") (name "Net-(U2A-CO4)") (class "Default")
      (node (ref "RN20") (pin "4") (pinfunction "4_4") (pintype "passive"))
      (node (ref "U2") (pin "11") (pinfunction "CO4_11") (pintype "bidirectional"))
    )
    (net (code "90") (name "VCC@1.8V") (class "Default")
      (node (ref "C10") (pin "1") (pinfunction "1_1") (pintype "passive"))
      (node (ref "C12") (pin "1") (pinfunction "1_1") (pintype "passive"))
      (node (ref "C3") (pin "1") (pinfunction "1_1") (pintype "passive"))
      (node (ref "C32") (pin "1") (pinfunction "1_1") (pintype "passive"))
      (node (ref "FB2") (pin "2") (pinfunction "2_2") (pintype "passive"))
      (node (ref "J1") (pin "1") (pinfunction "1_1") (pintype "passive"))
      (node (ref "U1") (pin "13") (pinfunction "VCCINT_13") (pintype "power_in"))
      (node (ref "U1") (pin "63") (pinfunction "VCCINT_63") (pintype "power_in"))
      (node (ref "U3") (pin "5") (pinfunction "OUT_5") (pintype "passive"))
    )
    (net (code "91") (name "VCC@3.3V") (class "Default")
      (node (ref "C14") (pin "1") (pinfunction "1_1") (pintype "passive"))
      (node (ref "C15") (pin "1") (pinfunction "1_1") (pintype "passive"))
      (node (ref "C16") (pin "1") (pinfunction "1_1") (pintype "passive"))
      (node (ref "C17") (pin "1") (pinfunction "1_1") (pintype "passive"))
      (node (ref "C18") (pin "1") (pinfunction "1_1") (pintype "passive"))
      (node (ref "C19") (pin "1") (pinfunction "1_1") (pintype "passive"))
      (node (ref "C2") (pin "1") (pinfunction "1_1") (pintype "passive"))
      (node (ref "C21") (pin "1") (pinfunction "1_1") (pintype "passive"))
      (node (ref "C22") (pin "1") (pinfunction "1_1") (pintype "passive"))
      (node (ref "C22A") (pin "1") (pinfunction "1_1") (pintype "passive"))
      (node (ref "C31") (pin "1") (pinfunction "1_1") (pintype "passive"))
      (node (ref "FB1") (pin "2") (pinfunction "2_2") (pintype "passive"))
      (node (ref "FB2") (pin "1") (pinfunction "1_1") (pintype "passive"))
      (node (ref "L1") (pin "2") (pinfunction "2_2") (pintype "passive"))
      (node (ref "R11") (pin "1") (pinfunction "1_1") (pintype "passive"))
      (node (ref "R12") (pin "1") (pinfunction "1_1") (pintype "passive"))
      (node (ref "U1") (pin "31") (pinfunction "VCCIO_31") (pintype "power_in"))
      (node (ref "U1") (pin "45") (pinfunction "VCCIO_45") (pintype "power_in"))
      (node (ref "U1") (pin "59") (pinfunction "VCCIO_59") (pintype "power_in"))
      (node (ref "U1") (pin "80") (pinfunction "VCCIO_80") (pintype "power_in"))
      (node (ref "U1") (pin "9") (pinfunction "VCCIO_9") (pintype "power_in"))
      (node (ref "U1") (pin "94") (pinfunction "VCCIO_94") (pintype "power_in"))
      (node (ref "U2") (pin "10") (pinfunction "VCC_10") (pintype "bidirectional"))
      (node (ref "U3") (pin "1") (pinfunction "IN_1") (pintype "input"))
      (node (ref "U3") (pin "3") (pinfunction "~{EN}_3") (pintype "input"))
    )
    (net (code "92") (name "VCCINT") (class "Default")
      (node (ref "C11") (pin "1") (pinfunction "1_1") (pintype "passive"))
      (node (ref "C13") (pin "1") (pinfunction "1_1") (pintype "passive"))
      (node (ref "J1") (pin "2") (pinfunction "2_2") (pintype "passive"))
      (node (ref "U1") (pin "39") (pinfunction "VCCINT_39") (pintype "power_in"))
      (node (ref "U1") (pin "88") (pinfunction "VCCINT_88") (pintype "power_in"))
    )
    (net (code "93") (name "unconnected-(FBN10-Pad4)") (class "Default")
      (node (ref "FBN10") (pin "4") (pinfunction "4_4") (pintype "passive"))
    )
    (net (code "94") (name "unconnected-(FBN10-Pad5)") (class "Default")
      (node (ref "FBN10") (pin "5") (pinfunction "5_5") (pintype "passive"))
    )
    (net (code "95") (name "unconnected-(FBN11-Pad1)") (class "Default")
      (node (ref "FBN11") (pin "1") (pinfunction "1_1") (pintype "passive"))
    )
    (net (code "96") (name "unconnected-(FBN11-Pad8)") (class "Default")
      (node (ref "FBN11") (pin "8") (pinfunction "8_8") (pintype "passive"))
    )
    (net (code "97") (name "unconnected-(FBN12-Pad1)") (class "Default")
      (node (ref "FBN12") (pin "1") (pinfunction "1_1") (pintype "passive"))
    )
    (net (code "98") (name "unconnected-(FBN12-Pad8)") (class "Default")
      (node (ref "FBN12") (pin "8") (pinfunction "8_8") (pintype "passive"))
    )
    (net (code "99") (name "unconnected-(FBN13-Pad1)") (class "Default")
      (node (ref "FBN13") (pin "1") (pinfunction "1_1") (pintype "passive"))
    )
    (net (code "100") (name "unconnected-(FBN13-Pad8)") (class "Default")
      (node (ref "FBN13") (pin "8") (pinfunction "8_8") (pintype "passive"))
    )
    (net (code "101") (name "unconnected-(RN101-Pad1)") (class "Default")
      (node (ref "RN101") (pin "1") (pinfunction "1_1") (pintype "passive"))
    )
    (net (code "102") (name "unconnected-(RN101-Pad8)") (class "Default")
      (node (ref "RN101") (pin "8") (pinfunction "8_8") (pintype "passive"))
    )
    (net (code "103") (name "unconnected-(RN111-Pad4)") (class "Default")
      (node (ref "RN111") (pin "4") (pinfunction "4_4") (pintype "passive"))
    )
    (net (code "104") (name "unconnected-(RN111-Pad5)") (class "Default")
      (node (ref "RN111") (pin "5") (pinfunction "5_5") (pintype "passive"))
    )
    (net (code "105") (name "unconnected-(RN121-Pad4)") (class "Default")
      (node (ref "RN121") (pin "4") (pinfunction "4_4") (pintype "passive"))
    )
    (net (code "106") (name "unconnected-(RN121-Pad5)") (class "Default")
      (node (ref "RN121") (pin "5") (pinfunction "5_5") (pintype "passive"))
    )
    (net (code "107") (name "unconnected-(U1-B1{slash}1-Pad3)") (class "Default")
      (node (ref "U1") (pin "3") (pinfunction "B1/1_3") (pintype "bidirectional"))
    )
    (net (code "108") (name "unconnected-(U1-B1{slash}2-Pad4)") (class "Default")
      (node (ref "U1") (pin "4") (pinfunction "B1/2_4") (pintype "bidirectional"))
    )
    (net (code "109") (name "unconnected-(U1-B1{slash}3-Pad5)") (class "Default")
      (node (ref "U1") (pin "5") (pinfunction "B1/3_5") (pintype "bidirectional"))
    )
    (net (code "110") (name "unconnected-(U1-B1{slash}4-Pad6)") (class "Default")
      (node (ref "U1") (pin "6") (pinfunction "B1/4_6") (pintype "bidirectional"))
    )
    (net (code "111") (name "unconnected-(U1-B1{slash}5-Pad7)") (class "Default")
      (node (ref "U1") (pin "7") (pinfunction "B1/5_7") (pintype "bidirectional"))
    )
    (net (code "112") (name "unconnected-(U1-B1{slash}24-TDO-Pad25)") (class "Default")
      (node (ref "U1") (pin "25") (pinfunction "B1/24-TDO_25") (pintype "output"))
    )
    (net (code "113") (name "unconnected-(U1-B1{slash}34-Pad35)") (class "Default")
      (node (ref "U1") (pin "35") (pinfunction "B1/34_35") (pintype "bidirectional"))
    )
    (net (code "114") (name "unconnected-(U1-B1{slash}35-Pad36)") (class "Default")
      (node (ref "U1") (pin "36") (pinfunction "B1/35_36") (pintype "bidirectional"))
    )
    (net (code "115") (name "unconnected-(U1-B1{slash}37-Pad38)") (class "Default")
      (node (ref "U1") (pin "38") (pinfunction "B1/37_38") (pintype "bidirectional"))
    )
    (net (code "116") (name "unconnected-(U1-B1{slash}39-Pad40)") (class "Default")
      (node (ref "U1") (pin "40") (pinfunction "B1/39_40") (pintype "bidirectional"))
    )
    (net (code "117") (name "unconnected-(U1-B1{slash}40-Pad41)") (class "Default")
      (node (ref "U1") (pin "41") (pinfunction "B1/40_41") (pintype "bidirectional"))
    )
    (net (code "118") (name "unconnected-(U1-B1{slash}41-Pad42)") (class "Default")
      (node (ref "U1") (pin "42") (pinfunction "B1/41_42") (pintype "bidirectional"))
    )
    (net (code "119") (name "unconnected-(U1-B2{slash}51-Pad52)") (class "Default")
      (node (ref "U1") (pin "52") (pinfunction "B2/51_52") (pintype "bidirectional"))
    )
    (net (code "120") (name "unconnected-(U1-B2{slash}53-Pad54)") (class "Default")
      (node (ref "U1") (pin "54") (pinfunction "B2/53_54") (pintype "bidirectional"))
    )
    (net (code "121") (name "unconnected-(U1-B2{slash}54-Pad55)") (class "Default")
      (node (ref "U1") (pin "55") (pinfunction "B2/54_55") (pintype "bidirectional"))
    )
    (net (code "122") (name "unconnected-(U1-B2{slash}55-Pad56)") (class "Default")
      (node (ref "U1") (pin "56") (pinfunction "B2/55_56") (pintype "bidirectional"))
    )
    (net (code "123") (name "unconnected-(U1-B2{slash}56-Pad57)") (class "Default")
      (node (ref "U1") (pin "57") (pinfunction "B2/56_57") (pintype "bidirectional"))
    )
    (net (code "124") (name "unconnected-(U1-B2{slash}57-Pad58)") (class "Default")
      (node (ref "U1") (pin "58") (pinfunction "B2/57_58") (pintype "bidirectional"))
    )
    (net (code "125") (name "unconnected-(U1-B2{slash}60-Pad61)") (class "Default")
      (node (ref "U1") (pin "61") (pinfunction "B2/60_61") (pintype "bidirectional"))
    )
    (net (code "126") (name "unconnected-(U1-B2{slash}61-GCLK2-Pad62)") (class "Default")
      (node (ref "U1") (pin "62") (pinfunction "B2/61-GCLK2_62") (pintype "bidirectional"))
    )
    (net (code "127") (name "unconnected-(U1-B2{slash}63-GCLK3-Pad64)") (class "Default")
      (node (ref "U1") (pin "64") (pinfunction "B2/63-GCLK3_64") (pintype "bidirectional"))
    )
    (net (code "128") (name "unconnected-(U1-B2{slash}66-Pad67)") (class "Default")
      (node (ref "U1") (pin "67") (pinfunction "B2/66_67") (pintype "bidirectional"))
    )
    (net (code "129") (name "unconnected-(U1-B2{slash}80-Pad81)") (class "Default")
      (node (ref "U1") (pin "81") (pinfunction "B2/80_81") (pintype "bidirectional"))
    )
    (net (code "130") (name "unconnected-(U1-B2{slash}81-Pad82)") (class "Default")
      (node (ref "U1") (pin "82") (pinfunction "B2/81_82") (pintype "bidirectional"))
    )
    (net (code "131") (name "unconnected-(U1-B2{slash}82-Pad83)") (class "Default")
      (node (ref "U1") (pin "83") (pinfunction "B2/82_83") (pintype "bidirectional"))
    )
    (net (code "132") (name "unconnected-(U1-B2{slash}83-Pad84)") (class "Default")
      (node (ref "U1") (pin "84") (pinfunction "B2/83_84") (pintype "bidirectional"))
    )
    (net (code "133") (name "unconnected-(U1-B2{slash}84-Pad85)") (class "Default")
      (node (ref "U1") (pin "85") (pinfunction "B2/84_85") (pintype "bidirectional"))
    )
    (net (code "134") (name "unconnected-(U1-B2{slash}85-Pad86)") (class "Default")
      (node (ref "U1") (pin "86") (pinfunction "B2/85_86") (pintype "bidirectional"))
    )
    (net (code "135") (name "unconnected-(U1-B2{slash}86-Pad87)") (class "Default")
      (node (ref "U1") (pin "87") (pinfunction "B2/86_87") (pintype "bidirectional"))
    )
    (net (code "136") (name "unconnected-(U1-B2{slash}88-Pad89)") (class "Default")
      (node (ref "U1") (pin "89") (pinfunction "B2/88_89") (pintype "bidirectional"))
    )
    (net (code "137") (name "unconnected-(U1-B2{slash}91-Pad92)") (class "Default")
      (node (ref "U1") (pin "92") (pinfunction "B2/91_92") (pintype "bidirectional"))
    )
    (net (code "138") (name "unconnected-(U1-B2{slash}95-Pad96)") (class "Default")
      (node (ref "U1") (pin "96") (pinfunction "B2/95_96") (pintype "bidirectional"))
    )
    (net (code "139") (name "unconnected-(U1-B2{slash}96-Pad97)") (class "Default")
      (node (ref "U1") (pin "97") (pinfunction "B2/96_97") (pintype "bidirectional"))
    )
    (net (code "140") (name "unconnected-(U3-NC{slash}FB-Pad4)") (class "Default")
      (node (ref "U3") (pin "4") (pinfunction "NC/FB_4") (pintype "passive"))
    )
  )
)
